# ANSIN.net
KiCad netlist of a schematic drawn in Altium Designer
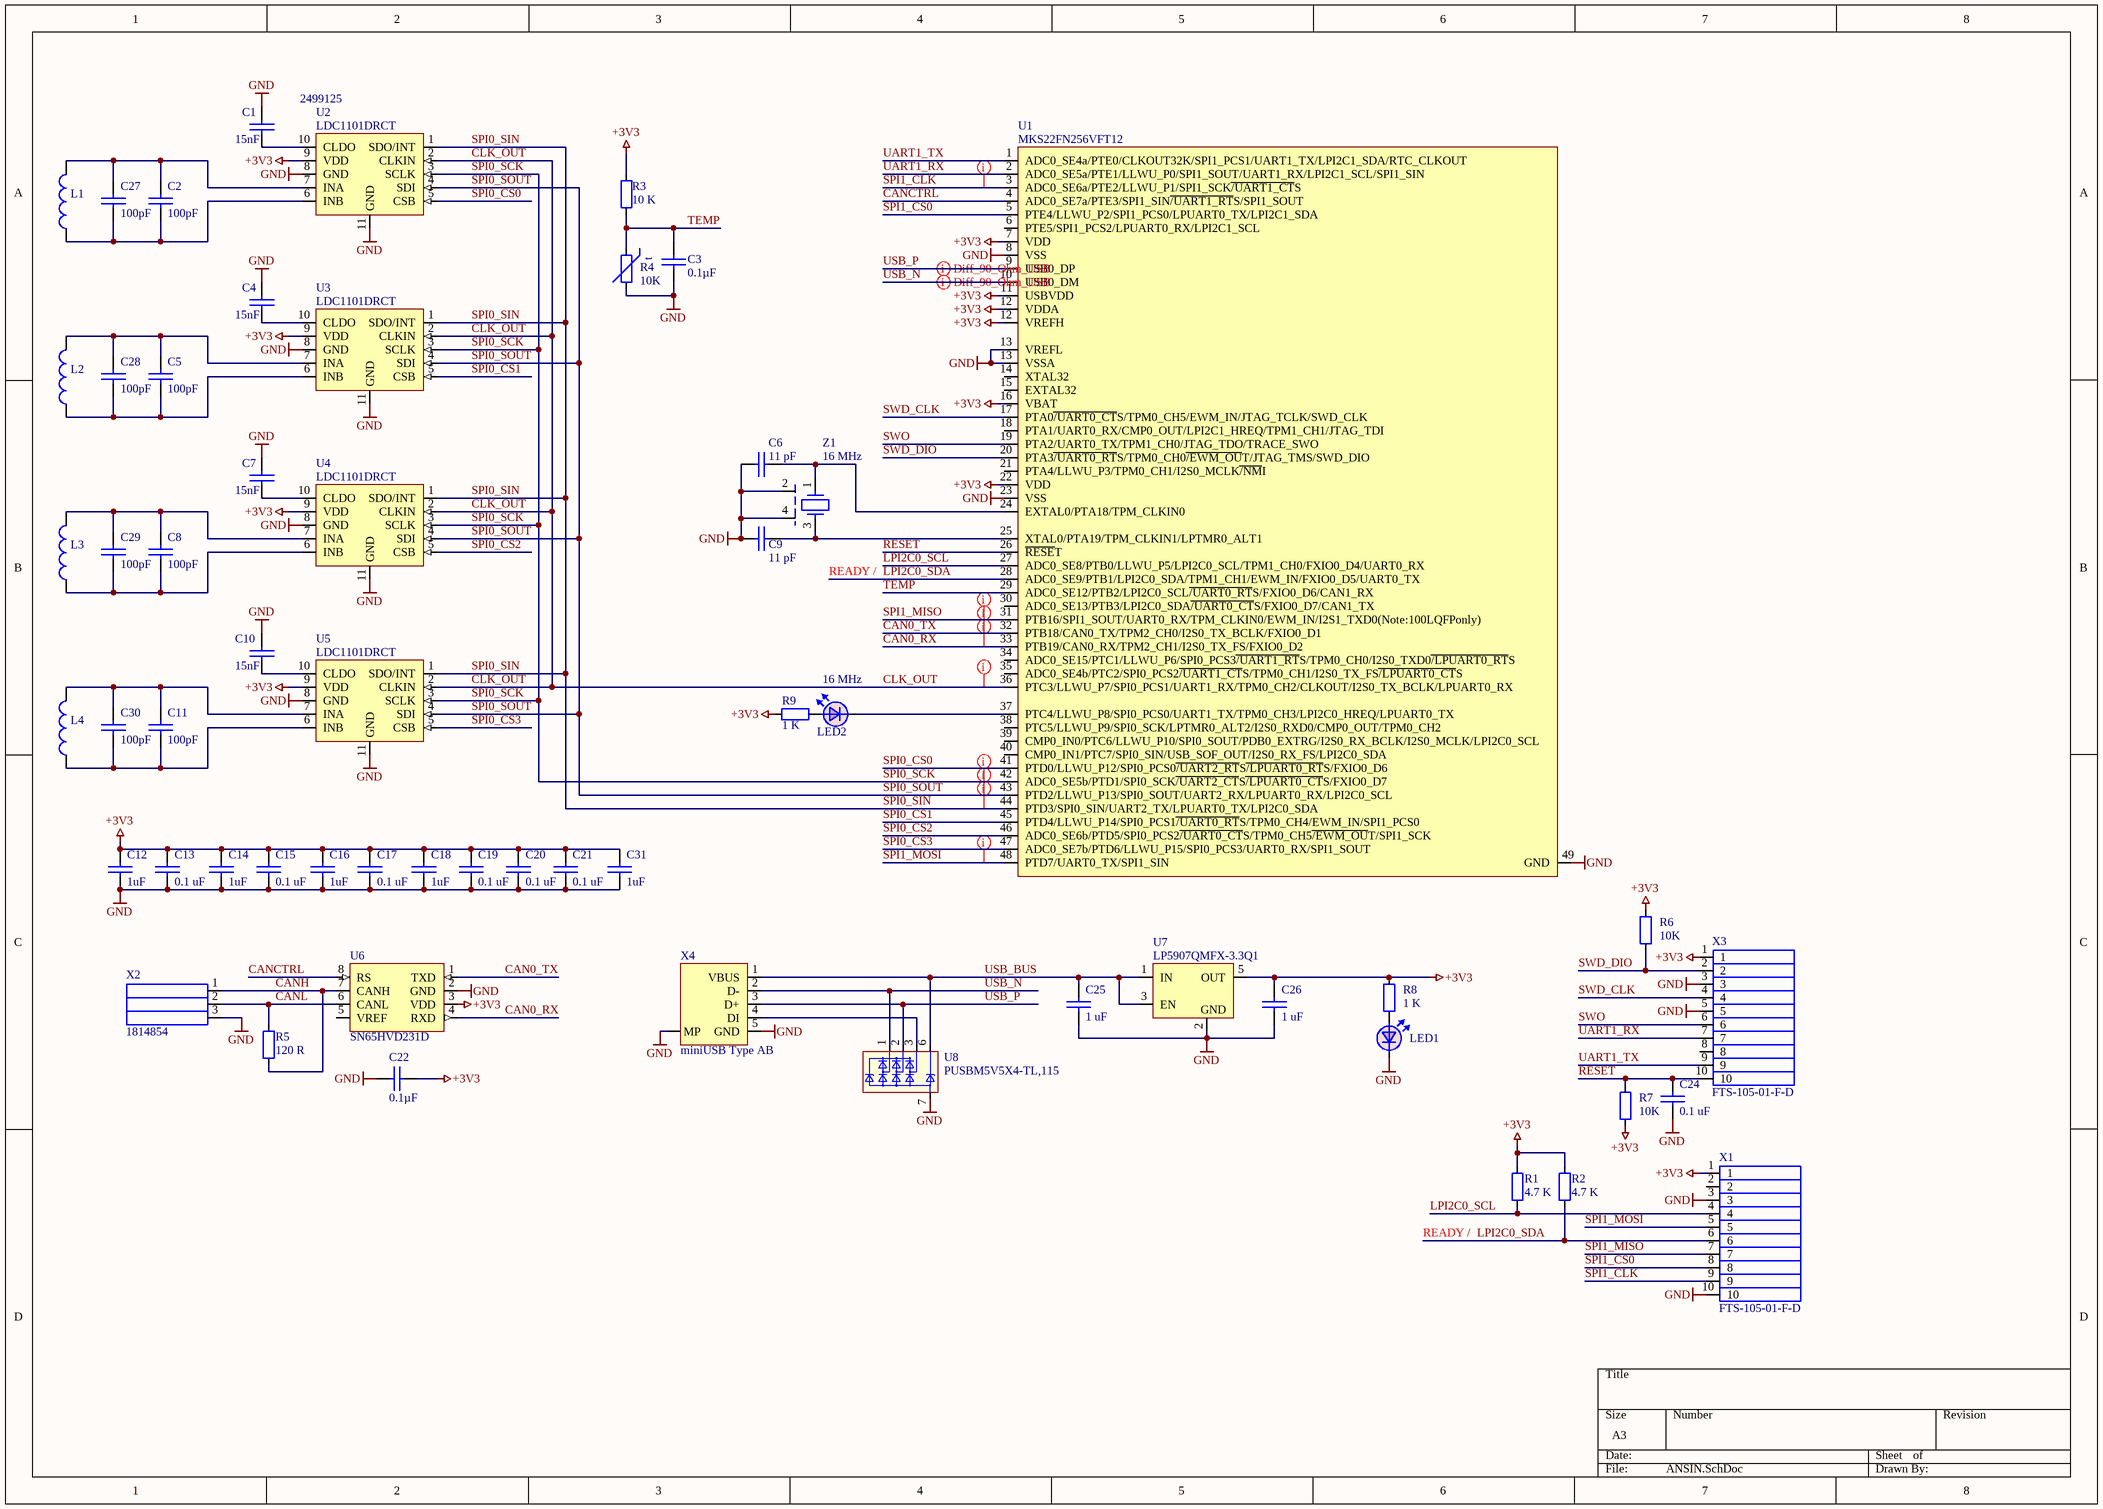
[diagram p0: ANSIN.SchDoc]

(export (version "E")
  (design (tool "Eeschema 10.0.6"))
  (components
    (comp (ref "C1")
      (value "15nF")
      (footprint "1005[0402]")
      (description "15 nF ±10%, 50V, X7R 0402, -55°C ~ 125°C")
      (fields
        (field (name "TOLERANCE") "±10%")
        (field (name "MANUFACTURER") "Murata Electronics North America")
      )
      (libsource (lib "ea_Capacitors") (part "GRM155R71H153KA12J"))
    )
    (comp (ref "C2")
      (value "100pF")
      (footprint "1005[0402]")
      (description "100pF ±1% 25V,High Q, C0G, NP0 0402")
      (fields (field (name "TOLERANCE") "±1%") (field (name "MANUFACTURER") "Kemet"))
      (libsource (lib "ea_Capacitors") (part "CBR04C101F3GAC"))
    )
    (comp (ref "C3")
      (value "0.1µF")
      (footprint "1608[0603]")
      (description "0.1 uF, 50V, 10% , X7R,  0603 SMD MLC Capacitor")
      (fields (field (name "TOLERANCE") "± 10%") (field (name "MANUFACTURER") "WALSIN"))
      (libsource (lib "ea_Capacitors") (part "CVNF100K0603-25"))
    )
    (comp (ref "C4")
      (value "15nF")
      (footprint "1005[0402]")
      (description "15 nF ±10%, 50V, X7R 0402, -55°C ~ 125°C")
      (fields
        (field (name "TOLERANCE") "±10%")
        (field (name "MANUFACTURER") "Murata Electronics North America")
      )
      (libsource (lib "ea_Capacitors") (part "GRM155R71H153KA12J"))
    )
    (comp (ref "C5")
      (value "100pF")
      (footprint "1005[0402]")
      (description "100pF ±1% 25V,High Q, C0G, NP0 0402")
      (fields (field (name "TOLERANCE") "±1%") (field (name "MANUFACTURER") "Kemet"))
      (libsource (lib "ea_Capacitors") (part "CBR04C101F3GAC"))
    )
    (comp (ref "C6")
      (value "11 pF")
      (footprint "1005[0402]")
      (description "11 pF, 25V, +-1%, NP0/COG, 0402, -55..+125")
      (fields (field (name "MANUFACTURER") "AVX Corporation") (field (name "TOLERANCE") "+-1%"))
      (libsource (lib "ea_Capacitors") (part "04023U110FAT2A"))
    )
    (comp (ref "C7")
      (value "15nF")
      (footprint "1005[0402]")
      (description "15 nF ±10%, 50V, X7R 0402, -55°C ~ 125°C")
      (fields
        (field (name "TOLERANCE") "±10%")
        (field (name "MANUFACTURER") "Murata Electronics North America")
      )
      (libsource (lib "ea_Capacitors") (part "GRM155R71H153KA12J"))
    )
    (comp (ref "C8")
      (value "100pF")
      (footprint "1005[0402]")
      (description "100pF ±1% 25V,High Q, C0G, NP0 0402")
      (fields (field (name "TOLERANCE") "±1%") (field (name "MANUFACTURER") "Kemet"))
      (libsource (lib "ea_Capacitors") (part "CBR04C101F3GAC"))
    )
    (comp (ref "C9")
      (value "11 pF")
      (footprint "1005[0402]")
      (description "11 pF, 25V, +-1%, NP0/COG, 0402, -55..+125")
      (fields (field (name "MANUFACTURER") "AVX Corporation") (field (name "TOLERANCE") "+-1%"))
      (libsource (lib "ea_Capacitors") (part "04023U110FAT2A"))
    )
    (comp (ref "C10")
      (value "15nF")
      (footprint "1005[0402]")
      (description "15 nF ±10%, 50V, X7R 0402, -55°C ~ 125°C")
      (fields
        (field (name "TOLERANCE") "±10%")
        (field (name "MANUFACTURER") "Murata Electronics North America")
      )
      (libsource (lib "ea_Capacitors") (part "GRM155R71H153KA12J"))
    )
    (comp (ref "C11")
      (value "100pF")
      (footprint "1005[0402]")
      (description "100pF ±1% 25V,High Q, C0G, NP0 0402")
      (fields (field (name "TOLERANCE") "±1%") (field (name "MANUFACTURER") "Kemet"))
      (libsource (lib "ea_Capacitors") (part "CBR04C101F3GAC"))
    )
    (comp (ref "C12")
      (value "1uF")
      (footprint "1005[0402]")
      (description "1 µF ±10% 16V, Low ESL X6S, 0402")
      (fields (field (name "TOLERANCE") "±10%") (field (name "MANUFACTURER") "TDK Corporation"))
      (libsource (lib "ea_Capacitors") (part "C1005X6S1C105K050BC"))
    )
    (comp (ref "C13")
      (value "0.1 uF")
      (footprint "1005[0402]")
      (description "0.1 uF, 10V, 10% , X5R,  0402, -55°C ~ 85°C")
      (fields (field (name "TOLERANCE") "+-10%") (field (name "MANUFACTURER") "Kemet"))
      (libsource (lib "ea_Capacitors") (part "C0402C104K8PACTU"))
    )
    (comp (ref "C14")
      (value "1uF")
      (footprint "1005[0402]")
      (description "1 µF ±10% 16V, Low ESL X6S, 0402")
      (fields (field (name "TOLERANCE") "±10%") (field (name "MANUFACTURER") "TDK Corporation"))
      (libsource (lib "ea_Capacitors") (part "C1005X6S1C105K050BC"))
    )
    (comp (ref "C15")
      (value "0.1 uF")
      (footprint "1005[0402]")
      (description "0.1 uF, 10V, 10% , X5R,  0402, -55°C ~ 85°C")
      (fields (field (name "TOLERANCE") "+-10%") (field (name "MANUFACTURER") "Kemet"))
      (libsource (lib "ea_Capacitors") (part "C0402C104K8PACTU"))
    )
    (comp (ref "C16")
      (value "1uF")
      (footprint "1005[0402]")
      (description "1 µF ±10% 16V, Low ESL X6S, 0402")
      (fields (field (name "TOLERANCE") "±10%") (field (name "MANUFACTURER") "TDK Corporation"))
      (libsource (lib "ea_Capacitors") (part "C1005X6S1C105K050BC"))
    )
    (comp (ref "C17")
      (value "0.1 uF")
      (footprint "1005[0402]")
      (description "0.1 uF, 10V, 10% , X5R,  0402, -55°C ~ 85°C")
      (fields (field (name "TOLERANCE") "+-10%") (field (name "MANUFACTURER") "Kemet"))
      (libsource (lib "ea_Capacitors") (part "C0402C104K8PACTU"))
    )
    (comp (ref "C18")
      (value "1uF")
      (footprint "1005[0402]")
      (description "1 µF ±10% 16V, Low ESL X6S, 0402")
      (fields (field (name "TOLERANCE") "±10%") (field (name "MANUFACTURER") "TDK Corporation"))
      (libsource (lib "ea_Capacitors") (part "C1005X6S1C105K050BC"))
    )
    (comp (ref "C19")
      (value "0.1 uF")
      (footprint "1005[0402]")
      (description "0.1 uF, 10V, 10% , X5R,  0402, -55°C ~ 85°C")
      (fields (field (name "TOLERANCE") "+-10%") (field (name "MANUFACTURER") "Kemet"))
      (libsource (lib "ea_Capacitors") (part "C0402C104K8PACTU"))
    )
    (comp (ref "C20")
      (value "0.1 uF")
      (footprint "1005[0402]")
      (description "0.1 uF, 10V, 10% , X5R,  0402, -55°C ~ 85°C")
      (fields (field (name "TOLERANCE") "+-10%") (field (name "MANUFACTURER") "Kemet"))
      (libsource (lib "ea_Capacitors") (part "C0402C104K8PACTU"))
    )
    (comp (ref "C21")
      (value "0.1 uF")
      (footprint "1005[0402]")
      (description "0.1 uF, 10V, 10% , X5R,  0402, -55°C ~ 85°C")
      (fields (field (name "TOLERANCE") "+-10%") (field (name "MANUFACTURER") "Kemet"))
      (libsource (lib "ea_Capacitors") (part "C0402C104K8PACTU"))
    )
    (comp (ref "C22")
      (value "0.1µF")
      (footprint "1608[0603]")
      (description "0.1 uF, 50V, 10% , X7R,  0603 SMD MLC Capacitor")
      (fields (field (name "TOLERANCE") "± 10%") (field (name "MANUFACTURER") "WALSIN"))
      (libsource (lib "ea_Capacitors") (part "CVNF100K0603-25"))
    )
    (comp (ref "C24")
      (value "0.1 uF")
      (footprint "1005[0402]")
      (description "0.1 uF, 10V, 10% , X5R,  0402, -55°C ~ 85°C")
      (fields (field (name "TOLERANCE") "+-10%") (field (name "MANUFACTURER") "Kemet"))
      (libsource (lib "ea_Capacitors") (part "C0402C104K8PACTU"))
    )
    (comp (ref "C25")
      (value "1 uF")
      (footprint "1608[0603]")
      (description "1.0 uF, 16V, 10%, X5R, 0603, -55..85 С")
      (fields (field (name "TOLERANCE") "10%") (field (name "MANUFACTURER") "Samsung"))
      (libsource (lib "ea_Capacitors") (part "CL10A105KO8NNNC"))
    )
    (comp (ref "C26")
      (value "1 uF")
      (footprint "1608[0603]")
      (description "1.0 uF, 16V, 10%, X5R, 0603, -55..85 С")
      (fields (field (name "TOLERANCE") "10%") (field (name "MANUFACTURER") "Samsung"))
      (libsource (lib "ea_Capacitors") (part "CL10A105KO8NNNC"))
    )
    (comp (ref "C27")
      (value "100pF")
      (footprint "1005[0402]")
      (description "100pF ±1% 25V,High Q, C0G, NP0 0402")
      (fields (field (name "TOLERANCE") "±1%") (field (name "MANUFACTURER") "Kemet"))
      (libsource (lib "ea_Capacitors") (part "CBR04C101F3GAC"))
    )
    (comp (ref "C28")
      (value "100pF")
      (footprint "1005[0402]")
      (description "100pF ±1% 25V,High Q, C0G, NP0 0402")
      (fields (field (name "TOLERANCE") "±1%") (field (name "MANUFACTURER") "Kemet"))
      (libsource (lib "ea_Capacitors") (part "CBR04C101F3GAC"))
    )
    (comp (ref "C29")
      (value "100pF")
      (footprint "1005[0402]")
      (description "100pF ±1% 25V,High Q, C0G, NP0 0402")
      (fields (field (name "TOLERANCE") "±1%") (field (name "MANUFACTURER") "Kemet"))
      (libsource (lib "ea_Capacitors") (part "CBR04C101F3GAC"))
    )
    (comp (ref "C30")
      (value "100pF")
      (footprint "1005[0402]")
      (description "100pF ±1% 25V,High Q, C0G, NP0 0402")
      (fields (field (name "TOLERANCE") "±1%") (field (name "MANUFACTURER") "Kemet"))
      (libsource (lib "ea_Capacitors") (part "CBR04C101F3GAC"))
    )
    (comp (ref "C31")
      (value "1uF")
      (footprint "1005[0402]")
      (description "1 µF ±10% 16V, Low ESL X6S, 0402")
      (fields (field (name "TOLERANCE") "±10%") (field (name "MANUFACTURER") "TDK Corporation"))
      (libsource (lib "ea_Capacitors") (part "C1005X6S1C105K050BC"))
    )
    (comp (ref "L1")
      (value "Coil")
      (footprint "Coil_4layers_8turns")
      (description "Coil_4layers_8turns")
      (libsource (lib "ea_SensorCoils") (part "Coil_4layers_8turns"))
    )
    (comp (ref "L2")
      (value "Coil")
      (footprint "Coil_4layers_8turns")
      (description "Coil_4layers_8turns")
      (libsource (lib "ea_SensorCoils") (part "Coil_4layers_8turns"))
    )
    (comp (ref "L3")
      (value "Coil")
      (footprint "Coil_4layers_8turns")
      (description "Coil_4layers_8turns")
      (libsource (lib "ea_SensorCoils") (part "Coil_4layers_8turns"))
    )
    (comp (ref "L4")
      (value "Coil")
      (footprint "Coil_4layers_8turns")
      (description "Coil_4layers_8turns")
      (libsource (lib "ea_SensorCoils") (part "Coil_4layers_8turns"))
    )
    (comp (ref "LED1")
      (value "SML-211UTT86")
      (footprint "0805 LED")
      (description "0805 red LED, hibright, 2 mA, 1.8V, 130°")
      (fields (field (name "MANUFACTURER") "Rohm") (field (name "PARTNUM") "511-1292-1-ND"))
      (libsource (lib "ea_Indicators") (part "SML-211UTT86"))
    )
    (comp (ref "LED2")
      (value "SML-211UTT86")
      (footprint "0805 LED")
      (description "0805 red LED, hibright, 2 mA, 1.8V, 130°")
      (fields (field (name "MANUFACTURER") "Rohm") (field (name "PARTNUM") "511-1292-1-ND"))
      (libsource (lib "ea_Indicators") (part "SML-211UTT86"))
    )
    (comp (ref "R1")
      (value "4.7 K")
      (footprint "0603")
      (description "4.7 K, 1%, 0603, SMD Resistor, Taped")
      (fields (field (name "MANUFACTURER") "Vishay") (field (name "TOLERANCE") "1%"))
      (libsource (lib "ea_Resistors") (part "RL0603K004.7-1"))
    )
    (comp (ref "R2")
      (value "4.7 K")
      (footprint "0603")
      (description "4.7 K, 1%, 0603, SMD Resistor, Taped")
      (fields (field (name "MANUFACTURER") "Vishay") (field (name "TOLERANCE") "1%"))
      (libsource (lib "ea_Resistors") (part "RL0603K004.7-1"))
    )
    (comp (ref "R3")
      (value "10 K")
      (footprint "0603")
      (description "10 K, 1%, 0603, SMD Resistor, Taped")
      (fields (field (name "MANUFACTURER") "Vishay Dale") (field (name "TOLERANCE") "1%"))
      (libsource (lib "ea_Resistors") (part "RL0603K010-1"))
    )
    (comp (ref "R4")
      (value "10K")
      (footprint "0805")
      (description "Thermistor 10k, 0805, NTC")
      (fields (field (name "MANUFACTURER") "Murata") (field (name "PARTNUM") "490-2456-1-ND"))
      (libsource (lib "ea_IC_sensors") (part "NCP21XV103J03RA"))
    )
    (comp (ref "R5")
      (value "120 R")
      (footprint "0603")
      (description "120 R, 1%, 0603, SMD Resistor, Taped")
      (fields (field (name "MANUFACTURER") "Vishay") (field (name "TOLERANCE") "1%"))
      (libsource (lib "ea_Resistors") (part "RL0603E120-1"))
    )
    (comp (ref "R6")
      (value "10K")
      (footprint "0402")
      (description "10 K, 0402, Thick Film, -55..+155")
      (fields (field (name "MANUFACTURER") "Rohm Semiconductor") (field (name "TOLERANCE") "5%"))
      (libsource (lib "ea_Resistors") (part "MCR01MZPJ103"))
    )
    (comp (ref "R7")
      (value "10K")
      (footprint "0402")
      (description "10 K, 0402, Thick Film, -55..+155")
      (fields (field (name "MANUFACTURER") "Rohm Semiconductor") (field (name "TOLERANCE") "5%"))
      (libsource (lib "ea_Resistors") (part "MCR01MZPJ103"))
    )
    (comp (ref "R8")
      (value "1 K")
      (footprint "0603")
      (description "1 K, 1%, 0603, SMD Resistor, Taped")
      (fields (field (name "MANUFACTURER") "Vishay") (field (name "TOLERANCE") "1%"))
      (libsource (lib "") (part "RL0603K001-1_1"))
    )
    (comp (ref "R9")
      (value "1 K")
      (footprint "0603")
      (description "1 K, 1%, 0603, SMD Resistor, Taped")
      (fields (field (name "MANUFACTURER") "Vishay") (field (name "TOLERANCE") "1%"))
      (libsource (lib "ea_Resistors") (part "RL0603K001-1"))
    )
    (comp (ref "U1")
      (value "MKS22FN256VFT12")
      (footprint "48-pin QFN NXP")
      (description "ARM® Cortex®-M4 Kinetis KS22 Microcontroller IC 32-Bit 120MHz 256KB (256K x 8) FLASH 48-QFN (7x7)")
      (fields (field (name "MANUFACTURER") "NXP USA Inc.") (field (name "PARTNUM") "MKS22FN256VFT12-ND"))
      (libsource (lib "ea_IC_CPU") (part "MKS22FN256VFT12"))
    )
    (comp (ref "U2")
      (value "LDC1101DRCT")
      (footprint "TI S-PVSON-N10")
      (description "Inductance-to-Digital Converter 16 b, 24 bit 150k, 180k SPI, -40°C ~ 125°C,  10-VSON (3x3)")
      (fields
        (field (name "MANUFACTURER") "Texas Instruments")
        (field (name "PARTNUM") "296-42280-1-ND")
        (field (name "SUPPLIER PART NUMBER 1") "2499125")
      )
      (libsource (lib "ea_IC_hall_gmr_sensors") (part "LDC1101DRCT"))
    )
    (comp (ref "U3")
      (value "LDC1101DRCT")
      (footprint "TI S-PVSON-N10")
      (description "Inductance-to-Digital Converter 16 b, 24 bit 150k, 180k SPI, -40°C ~ 125°C,  10-VSON (3x3)")
      (fields (field (name "MANUFACTURER") "Texas Instruments") (field (name "PARTNUM") "296-42280-1-ND"))
      (libsource (lib "ea_IC_hall_gmr_sensors") (part "LDC1101DRCT"))
    )
    (comp (ref "U4")
      (value "LDC1101DRCT")
      (footprint "TI S-PVSON-N10")
      (description "Inductance-to-Digital Converter 16 b, 24 bit 150k, 180k SPI, -40°C ~ 125°C,  10-VSON (3x3)")
      (fields (field (name "MANUFACTURER") "Texas Instruments") (field (name "PARTNUM") "296-42280-1-ND"))
      (libsource (lib "ea_IC_hall_gmr_sensors") (part "LDC1101DRCT"))
    )
    (comp (ref "U5")
      (value "LDC1101DRCT")
      (footprint "TI S-PVSON-N10")
      (description "Inductance-to-Digital Converter 16 b, 24 bit 150k, 180k SPI, -40°C ~ 125°C,  10-VSON (3x3)")
      (fields (field (name "MANUFACTURER") "Texas Instruments") (field (name "PARTNUM") "296-42280-1-ND"))
      (libsource (lib "ea_IC_hall_gmr_sensors") (part "LDC1101DRCT"))
    )
    (comp (ref "U6")
      (value "SN65HVD231D")
      (footprint "SO-8")
      (description "3.3-V CAN TRANSCEIVERS SO-8")
      (fields (field (name "MANUFACTURER") "Texas Instruments") (field (name "PARTNUM") "296-12206-5-ND"))
      (libsource (lib "ea_IC_Interfaces") (part "SN65HVD231D"))
    )
    (comp (ref "U7")
      (value "LP5907QMFX-3.3Q1")
      (footprint "SOT23-5")
      (description "LDO 3.3 V, 250 mA, Vin < 5.5V, Iq < 12uA, -40..+125 C, SOT23-5")
      (fields (field (name "MANUFACTURER") "Texas Instruments") (field (name "PARTNUM") "296-40365-1-ND"))
      (libsource (lib "ea_IC_Power_Reg_Ref_Sw") (part "LP5907QMFX-3.3Q1"))
    )
    (comp (ref "U8")
      (value "PUSBM5V5X4-TL,115")
      (footprint "DFN1616-6")
      (description "TVS DIODE 5.5VWM 12VC 6HXSON")
      (fields (field (name "MANUFACTURER") "NXP Semiconductors") (field (name "PARTNUM") "568-10921-1-ND"))
      (libsource (lib "ea_TVS_protection") (part "PUSBM5V5X4-TL,115"))
    )
    (comp (ref "X1")
      (value "FTS-105-01-F-D")
      (footprint "FTS-105-01-F-D")
      (description "Board-To-Board Connector, Vertical, FTS Series, Through Hole, Header, 10, 1.27 mm")
      (fields (field (name "MANUFACTURER") "SAMTEC") (field (name "PARTNUM") "1928242"))
      (libsource (lib "ea_JTAG_SWD") (part "FTS-105-01-F-D"))
    )
    (comp (ref "X2")
      (value "1814854")
      (footprint "1814854")
      (description "SSL Connector 3 Position Header, Male Pins Board to Cable/Wire 0.098\" (2.50mm) Solder")
      (fields (field (name "MANUFACTURER") "Phoenix Contact") (field (name "PARTNUM") "277-9957-1-ND"))
      (libsource (lib "ea_Connectors") (part "1814854"))
    )
    (comp (ref "X3")
      (value "FTS-105-01-F-D")
      (footprint "FTS-105-01-F-D")
      (description "Board-To-Board Connector, Vertical, FTS Series, Through Hole, Header, 10, 1.27 mm")
      (fields (field (name "MANUFACTURER") "SAMTEC") (field (name "PARTNUM") "1928242"))
      (libsource (lib "ea_JTAG_SWD") (part "FTS-105-01-F-D"))
    )
    (comp (ref "X4")
      (value "miniUSB Type AB")
      (footprint "USB AB 56579-0576 Molex")
      (description "SMD USB - OTG, miniUSB Type AB")
      (fields
        (field (name "MANUFACTURER") "Molex/Waldom Electronics Corp")
        (field (name "PARTNUM") "WM17122CT-ND")
      )
      (libsource (lib "ea_Connectors") (part "USB AB 56579-0576"))
    )
    (comp (ref "Z1")
      (value "16 MHz")
      (footprint "4-SMD 2.00mm x 1.60mm")
      (description "16 MHz, 9 pF, ±10ppm, 2.00mm x 1.60mm, -20°C ~ 70°C")
      (fields (field (name "MANUFACTURER") "Abracon LLC") (field (name "PARTNUM") "535-13598-1-ND"))
      (libsource (lib "ea_OSC_CLK_GEN") (part "ABM11-16.000MHZ-9-B1U-T"))
    )
  )
  (nets
    (net (code "1") (name "+3V3") (class "Default")
      (node (ref "C12") (pin "1") (pinfunction "1_1") (pintype "passive"))
      (node (ref "C13") (pin "1") (pinfunction "1_1") (pintype "passive"))
      (node (ref "C14") (pin "1") (pinfunction "1_1") (pintype "passive"))
      (node (ref "C15") (pin "1") (pinfunction "1_1") (pintype "passive"))
      (node (ref "C16") (pin "1") (pinfunction "1_1") (pintype "passive"))
      (node (ref "C17") (pin "1") (pinfunction "1_1") (pintype "passive"))
      (node (ref "C18") (pin "1") (pinfunction "1_1") (pintype "passive"))
      (node (ref "C19") (pin "1") (pinfunction "1_1") (pintype "passive"))
      (node (ref "C20") (pin "1") (pinfunction "1_1") (pintype "passive"))
      (node (ref "C21") (pin "1") (pinfunction "1_1") (pintype "passive"))
      (node (ref "C22") (pin "1") (pinfunction "1_1") (pintype "passive"))
      (node (ref "C26") (pin "1") (pinfunction "1_1") (pintype "passive"))
      (node (ref "C31") (pin "1") (pinfunction "1_1") (pintype "passive"))
      (node (ref "R1") (pin "2") (pinfunction "2_2") (pintype "passive"))
      (node (ref "R2") (pin "2") (pinfunction "2_2") (pintype "passive"))
      (node (ref "R3") (pin "2") (pinfunction "2_2") (pintype "passive"))
      (node (ref "R6") (pin "2") (pinfunction "2_2") (pintype "passive"))
      (node (ref "R7") (pin "1") (pinfunction "1_1") (pintype "passive"))
      (node (ref "R8") (pin "2") (pinfunction "2_2") (pintype "passive"))
      (node (ref "R9") (pin "2") (pinfunction "2_2") (pintype "passive"))
      (node (ref "U1") (pin "11") (pinfunction "USBVDD_11") (pintype "bidirectional"))
      (node (ref "U1") (pin "12") (pinfunction "VDDA_12") (pintype "power_in"))
      (node (ref "U1") (pin "16") (pinfunction "VBAT_16") (pintype "power_in"))
      (node (ref "U1") (pin "22") (pinfunction "VDD_22") (pintype "power_in"))
      (node (ref "U1") (pin "7") (pinfunction "VDD_7") (pintype "power_in"))
      (node (ref "U2") (pin "9") (pinfunction "VDD_9") (pintype "power_in"))
      (node (ref "U3") (pin "9") (pinfunction "VDD_9") (pintype "power_in"))
      (node (ref "U4") (pin "9") (pinfunction "VDD_9") (pintype "power_in"))
      (node (ref "U5") (pin "9") (pinfunction "VDD_9") (pintype "power_in"))
      (node (ref "U6") (pin "3") (pinfunction "VDD_3") (pintype "power_in"))
      (node (ref "U7") (pin "5") (pinfunction "OUT_5") (pintype "power_in"))
      (node (ref "X1") (pin "1") (pinfunction "1_1") (pintype "passive"))
      (node (ref "X3") (pin "1") (pinfunction "1_1") (pintype "passive"))
    )
    (net (code "2") (name "/CAN0_RX") (class "Default")
      (node (ref "U1") (pin "33") (pinfunction "PTB19/CAN0_RX/TPM2_CH1/I2S0_TX_FS/FXIO0_D2_33") (pintype "bidirectional"))
      (node (ref "U6") (pin "4") (pinfunction "RXD_4") (pintype "output"))
    )
    (net (code "3") (name "/CAN0_TX") (class "Default")
      (node (ref "U1") (pin "32") (pinfunction "PTB18/CAN0_TX/TPM2_CH0/I2S0_TX_BCLK/FXIO0_D1_32") (pintype "bidirectional"))
      (node (ref "U6") (pin "1") (pinfunction "TXD_1") (pintype "input"))
    )
    (net (code "4") (name "/CANCTRL") (class "Default")
      (node (ref "U1") (pin "4") (pinfunction "ADC0_SE7a/PTE3/SPI1_SIN~{/UART1_RT}S/SPI1_SOUT_4") (pintype "bidirectional"))
      (node (ref "U6") (pin "8") (pinfunction "RS_8") (pintype "input"))
    )
    (net (code "5") (name "/CANH") (class "Default")
      (node (ref "R5") (pin "1") (pinfunction "1_1") (pintype "passive"))
      (node (ref "U6") (pin "7") (pinfunction "CANH_7") (pintype "bidirectional"))
      (node (ref "X2") (pin "1") (pinfunction "1_1") (pintype "passive"))
    )
    (net (code "6") (name "/CANL") (class "Default")
      (node (ref "R5") (pin "2") (pinfunction "2_2") (pintype "passive"))
      (node (ref "U6") (pin "6") (pinfunction "CANL_6") (pintype "bidirectional"))
      (node (ref "X2") (pin "2") (pinfunction "2_2") (pintype "passive"))
    )
    (net (code "7") (name "/CLK_OUT") (class "Default")
      (node (ref "U1") (pin "36") (pinfunction "PTC3/LLWU_P7/SPI0_PCS1/UART1_RX/TPM0_CH2/CLKOUT/I2S0_TX_BCLK/LPUART0_RX_36") (pintype "bidirectional"))
      (node (ref "U2") (pin "2") (pinfunction "CLKIN_2") (pintype "input"))
      (node (ref "U3") (pin "2") (pinfunction "CLKIN_2") (pintype "input"))
      (node (ref "U4") (pin "2") (pinfunction "CLKIN_2") (pintype "input"))
      (node (ref "U5") (pin "2") (pinfunction "CLKIN_2") (pintype "input"))
    )
    (net (code "8") (name "/LPI2C0_SCL") (class "Default")
      (node (ref "R1") (pin "1") (pinfunction "1_1") (pintype "passive"))
      (node (ref "U1") (pin "27") (pinfunction "ADC0_SE8/PTB0/LLWU_P5/LPI2C0_SCL/TPM1_CH0/FXIO0_D4/UART0_RX_27") (pintype "bidirectional"))
      (node (ref "X1") (pin "4") (pinfunction "4_4") (pintype "passive"))
    )
    (net (code "9") (name "/LPI2C0_SDA") (class "Default")
      (node (ref "R2") (pin "1") (pinfunction "1_1") (pintype "passive"))
      (node (ref "U1") (pin "28") (pinfunction "ADC0_SE9/PTB1/LPI2C0_SDA/TPM1_CH1/EWM_IN/FXIO0_D5/UART0_TX_28") (pintype "bidirectional"))
      (node (ref "X1") (pin "6") (pinfunction "6_6") (pintype "power_in"))
    )
    (net (code "10") (name "/RESET") (class "Default")
      (node (ref "C24") (pin "1") (pinfunction "1_1") (pintype "passive"))
      (node (ref "R7") (pin "2") (pinfunction "2_2") (pintype "passive"))
      (node (ref "U1") (pin "26") (pinfunction "~{RESE}T_26") (pintype "bidirectional"))
      (node (ref "X3") (pin "10") (pinfunction "10_10") (pintype "power_in"))
    )
    (net (code "11") (name "/SPI0_CS0") (class "Default")
      (node (ref "U1") (pin "41") (pinfunction "PTD0/LLWU_P12/SPI0_PCS0~{/UART2_RT}S~{/LPUART0_RT}S/FXIO0_D6_41") (pintype "bidirectional"))
      (node (ref "U2") (pin "5") (pinfunction "CSB_5") (pintype "input"))
    )
    (net (code "12") (name "/SPI0_CS1") (class "Default")
      (node (ref "U1") (pin "45") (pinfunction "PTD4/LLWU_P14/SPI0_PCS1~{/UART0_RT}S/TPM0_CH4/EWM_IN/SPI1_PCS0_45") (pintype "bidirectional"))
      (node (ref "U3") (pin "5") (pinfunction "CSB_5") (pintype "input"))
    )
    (net (code "13") (name "/SPI0_CS2") (class "Default")
      (node (ref "U1") (pin "46") (pinfunction "ADC0_SE6b/PTD5/SPI0_PCS2~{/UART0_CT}S/TPM0_CH5~{/EWM_OU}T/SPI1_SCK_46") (pintype "bidirectional"))
      (node (ref "U4") (pin "5") (pinfunction "CSB_5") (pintype "input"))
    )
    (net (code "14") (name "/SPI0_CS3") (class "Default")
      (node (ref "U1") (pin "47") (pinfunction "ADC0_SE7b/PTD6/LLWU_P15/SPI0_PCS3/UART0_RX/SPI1_SOUT_47") (pintype "bidirectional"))
      (node (ref "U5") (pin "5") (pinfunction "CSB_5") (pintype "input"))
    )
    (net (code "15") (name "/SPI0_SCK") (class "Default")
      (node (ref "U1") (pin "42") (pinfunction "ADC0_SE5b/PTD1/SPI0_SCK~{/UART2_CT}S~{/LPUART0_CT}S/FXIO0_D7_42") (pintype "bidirectional"))
      (node (ref "U2") (pin "3") (pinfunction "SCLK_3") (pintype "input"))
      (node (ref "U3") (pin "3") (pinfunction "SCLK_3") (pintype "input"))
      (node (ref "U4") (pin "3") (pinfunction "SCLK_3") (pintype "input"))
      (node (ref "U5") (pin "3") (pinfunction "SCLK_3") (pintype "input"))
    )
    (net (code "16") (name "/SPI0_SIN") (class "Default")
      (node (ref "U1") (pin "44") (pinfunction "PTD3/SPI0_SIN/UART2_TX/LPUART0_TX/LPI2C0_SDA_44") (pintype "bidirectional"))
      (node (ref "U2") (pin "1") (pinfunction "SDO/INT_1") (pintype "tri_state"))
      (node (ref "U3") (pin "1") (pinfunction "SDO/INT_1") (pintype "tri_state"))
      (node (ref "U4") (pin "1") (pinfunction "SDO/INT_1") (pintype "tri_state"))
      (node (ref "U5") (pin "1") (pinfunction "SDO/INT_1") (pintype "tri_state"))
    )
    (net (code "17") (name "/SPI0_SOUT") (class "Default")
      (node (ref "U1") (pin "43") (pinfunction "PTD2/LLWU_P13/SPI0_SOUT/UART2_RX/LPUART0_RX/LPI2C0_SCL_43") (pintype "bidirectional"))
      (node (ref "U2") (pin "4") (pinfunction "SDI_4") (pintype "input"))
      (node (ref "U3") (pin "4") (pinfunction "SDI_4") (pintype "input"))
      (node (ref "U4") (pin "4") (pinfunction "SDI_4") (pintype "input"))
      (node (ref "U5") (pin "4") (pinfunction "SDI_4") (pintype "input"))
    )
    (net (code "18") (name "/SPI1_CLK") (class "Default")
      (node (ref "U1") (pin "3") (pinfunction "ADC0_SE6a/PTE2/LLWU_P1/SPI1_SCK~{/UART1_CT}S_3") (pintype "bidirectional"))
      (node (ref "X1") (pin "9") (pinfunction "9_9") (pintype "power_in"))
    )
    (net (code "19") (name "/SPI1_CS0") (class "Default")
      (node (ref "U1") (pin "5") (pinfunction "PTE4/LLWU_P2/SPI1_PCS0/LPUART0_TX/LPI2C1_SDA_5") (pintype "bidirectional"))
      (node (ref "X1") (pin "8") (pinfunction "8_8") (pintype "power_in"))
    )
    (net (code "20") (name "/SPI1_MISO") (class "Default")
      (node (ref "U1") (pin "31") (pinfunction "PTB16/SPI1_SOUT/UART0_RX/TPM_CLKIN0/EWM_IN/I2S1_TXD0(Note:100LQFPonly)_31") (pintype "bidirectional"))
      (node (ref "X1") (pin "7") (pinfunction "7_7") (pintype "power_in"))
    )
    (net (code "21") (name "/SPI1_MOSI") (class "Default")
      (node (ref "U1") (pin "48") (pinfunction "PTD7/UART0_TX/SPI1_SIN_48") (pintype "bidirectional"))
      (node (ref "X1") (pin "5") (pinfunction "5_5") (pintype "power_in"))
    )
    (net (code "22") (name "/SWD_CLK") (class "Default")
      (node (ref "U1") (pin "17") (pinfunction "PTA0~{/UART0_CT}S/TPM0_CH5/EWM_IN/JTAG_TCLK/SWD_CLK_17") (pintype "bidirectional"))
      (node (ref "X3") (pin "4") (pinfunction "4_4") (pintype "passive"))
    )
    (net (code "23") (name "/SWD_DIO") (class "Default")
      (node (ref "R6") (pin "1") (pinfunction "1_1") (pintype "passive"))
      (node (ref "U1") (pin "20") (pinfunction "PTA3~{/UART0_RT}S/TPM0_CH0~{/EWM_OU}T/JTAG_TMS/SWD_DIO_20") (pintype "bidirectional"))
      (node (ref "X3") (pin "2") (pinfunction "2_2") (pintype "passive"))
    )
    (net (code "24") (name "/SWO") (class "Default")
      (node (ref "U1") (pin "19") (pinfunction "PTA2/UART0_TX/TPM1_CH0/JTAG_TDO/TRACE_SWO_19") (pintype "bidirectional"))
      (node (ref "X3") (pin "6") (pinfunction "6_6") (pintype "power_in"))
    )
    (net (code "25") (name "/TEMP") (class "Default")
      (node (ref "C3") (pin "2") (pinfunction "2_2") (pintype "passive"))
      (node (ref "R3") (pin "1") (pinfunction "1_1") (pintype "passive"))
      (node (ref "R4") (pin "2") (pinfunction "2_2") (pintype "passive"))
      (node (ref "U1") (pin "29") (pinfunction "ADC0_SE12/PTB2/LPI2C0_SCL~{/UART0_RT}S/FXIO0_D6/CAN1_RX_29") (pintype "bidirectional"))
    )
    (net (code "26") (name "/UART1_RX") (class "Default")
      (node (ref "U1") (pin "2") (pinfunction "ADC0_SE5a/PTE1/LLWU_P0/SPI1_SOUT/UART1_RX/LPI2C1_SCL/SPI1_SIN_2") (pintype "bidirectional"))
      (node (ref "X3") (pin "7") (pinfunction "7_7") (pintype "power_in"))
    )
    (net (code "27") (name "/UART1_TX") (class "Default")
      (node (ref "U1") (pin "1") (pinfunction "ADC0_SE4a/PTE0/CLKOUT32K/SPI1_PCS1/UART1_TX/LPI2C1_SDA/RTC_CLKOUT_1") (pintype "bidirectional"))
      (node (ref "X3") (pin "9") (pinfunction "9_9") (pintype "power_in"))
    )
    (net (code "28") (name "/USB_BUS") (class "Default")
      (node (ref "C25") (pin "1") (pinfunction "1_1") (pintype "passive"))
      (node (ref "U7") (pin "1") (pinfunction "IN_1") (pintype "power_in"))
      (node (ref "U7") (pin "3") (pinfunction "EN_3") (pintype "power_in"))
      (node (ref "U8") (pin "6") (pinfunction "6_6") (pintype "passive"))
      (node (ref "X4") (pin "1") (pinfunction "VBUS_1") (pintype "power_in"))
    )
    (net (code "29") (name "/USB_N") (class "Default")
      (node (ref "U1") (pin "10") (pinfunction "USB0_DM_10") (pintype "bidirectional"))
      (node (ref "U8") (pin "1") (pinfunction "1_1") (pintype "passive"))
      (node (ref "X4") (pin "2") (pinfunction "D-_2") (pintype "bidirectional"))
    )
    (net (code "30") (name "/USB_P") (class "Default")
      (node (ref "U1") (pin "9") (pinfunction "USB0_DP_9") (pintype "bidirectional"))
      (node (ref "U8") (pin "2") (pinfunction "2_2") (pintype "passive"))
      (node (ref "X4") (pin "3") (pinfunction "D+_3") (pintype "bidirectional"))
    )
    (net (code "31") (name "GND") (class "Default")
      (node (ref "C1") (pin "1") (pinfunction "1_1") (pintype "passive"))
      (node (ref "C10") (pin "1") (pinfunction "1_1") (pintype "passive"))
      (node (ref "C12") (pin "2") (pinfunction "2_2") (pintype "passive"))
      (node (ref "C13") (pin "2") (pinfunction "2_2") (pintype "passive"))
      (node (ref "C14") (pin "2") (pinfunction "2_2") (pintype "passive"))
      (node (ref "C15") (pin "2") (pinfunction "2_2") (pintype "passive"))
      (node (ref "C16") (pin "2") (pinfunction "2_2") (pintype "passive"))
      (node (ref "C17") (pin "2") (pinfunction "2_2") (pintype "passive"))
      (node (ref "C18") (pin "2") (pinfunction "2_2") (pintype "passive"))
      (node (ref "C19") (pin "2") (pinfunction "2_2") (pintype "passive"))
      (node (ref "C20") (pin "2") (pinfunction "2_2") (pintype "passive"))
      (node (ref "C21") (pin "2") (pinfunction "2_2") (pintype "passive"))
      (node (ref "C22") (pin "2") (pinfunction "2_2") (pintype "passive"))
      (node (ref "C24") (pin "2") (pinfunction "2_2") (pintype "passive"))
      (node (ref "C25") (pin "2") (pinfunction "2_2") (pintype "passive"))
      (node (ref "C26") (pin "2") (pinfunction "2_2") (pintype "passive"))
      (node (ref "C3") (pin "1") (pinfunction "1_1") (pintype "passive"))
      (node (ref "C31") (pin "2") (pinfunction "2_2") (pintype "passive"))
      (node (ref "C4") (pin "1") (pinfunction "1_1") (pintype "passive"))
      (node (ref "C6") (pin "2") (pinfunction "2_2") (pintype "passive"))
      (node (ref "C7") (pin "1") (pinfunction "1_1") (pintype "passive"))
      (node (ref "C9") (pin "2") (pinfunction "2_2") (pintype "passive"))
      (node (ref "LED1") (pin "2") (pinfunction "2_2") (pintype "passive"))
      (node (ref "R4") (pin "1") (pinfunction "1_1") (pintype "passive"))
      (node (ref "U1") (pin "13") (pinfunction "VREFL_13") (pintype "bidirectional"))
      (node (ref "U1") (pin "23") (pinfunction "VSS_23") (pintype "power_in"))
      (node (ref "U1") (pin "49") (pinfunction "GND_49") (pintype "passive"))
      (node (ref "U1") (pin "8") (pinfunction "VSS_8") (pintype "power_in"))
      (node (ref "U2") (pin "11") (pinfunction "GND_11") (pintype "passive"))
      (node (ref "U2") (pin "8") (pinfunction "GND_8") (pintype "passive"))
      (node (ref "U3") (pin "11") (pinfunction "GND_11") (pintype "passive"))
      (node (ref "U3") (pin "8") (pinfunction "GND_8") (pintype "passive"))
      (node (ref "U4") (pin "11") (pinfunction "GND_11") (pintype "passive"))
      (node (ref "U4") (pin "8") (pinfunction "GND_8") (pintype "passive"))
      (node (ref "U5") (pin "11") (pinfunction "GND_11") (pintype "passive"))
      (node (ref "U5") (pin "8") (pinfunction "GND_8") (pintype "passive"))
      (node (ref "U6") (pin "2") (pinfunction "GND_2") (pintype "power_in"))
      (node (ref "U7") (pin "2") (pinfunction "GND_2") (pintype "power_in"))
      (node (ref "U8") (pin "7") (pinfunction "7_7") (pintype "passive"))
      (node (ref "X1") (pin "10") (pinfunction "10_10") (pintype "power_in"))
      (node (ref "X1") (pin "3") (pinfunction "3_3") (pintype "passive"))
      (node (ref "X2") (pin "3") (pinfunction "3_3") (pintype "passive"))
      (node (ref "X3") (pin "3") (pinfunction "3_3") (pintype "passive"))
      (node (ref "X3") (pin "5") (pinfunction "5_5") (pintype "power_in"))
      (node (ref "X4") (pin "5") (pinfunction "GND_5") (pintype "power_in"))
      (node (ref "X4") (pin "MP") (pinfunction "MP_MP") (pintype "passive"))
      (node (ref "Z1") (pin "2") (pinfunction "2_2") (pintype "passive"))
      (node (ref "Z1") (pin "4") (pinfunction "4_4") (pintype "passive"))
    )
    (net (code "32") (name "Net-(LED1-Pad1)") (class "Default")
      (node (ref "LED1") (pin "1") (pinfunction "1_1") (pintype "passive"))
      (node (ref "R8") (pin "1") (pinfunction "1_1") (pintype "passive"))
    )
    (net (code "33") (name "Net-(LED2-Pad1)") (class "Default")
      (node (ref "LED2") (pin "1") (pinfunction "1_1") (pintype "passive"))
      (node (ref "R9") (pin "1") (pinfunction "1_1") (pintype "passive"))
    )
    (net (code "34") (name "Net-(U1-EXTAL0{slash}PTA18{slash}TPM_CLKIN0)") (class "Default")
      (node (ref "C6") (pin "1") (pinfunction "1_1") (pintype "passive"))
      (node (ref "U1") (pin "24") (pinfunction "EXTAL0/PTA18/TPM_CLKIN0_24") (pintype "bidirectional"))
      (node (ref "Z1") (pin "1") (pinfunction "1_1") (pintype "passive"))
    )
    (net (code "35") (name "Net-(U1-PTC4{slash}LLWU_P8{slash}SPI0_PCS0{slash}UART1_TX{slash}TPM0_CH3{slash}LPI2C0_HREQ{slash}LPUART0_TX)") (class "Default")
      (node (ref "LED2") (pin "2") (pinfunction "2_2") (pintype "passive"))
      (node (ref "U1") (pin "37") (pinfunction "PTC4/LLWU_P8/SPI0_PCS0/UART1_TX/TPM0_CH3/LPI2C0_HREQ/LPUART0_TX_37") (pintype "bidirectional"))
    )
    (net (code "36") (name "Net-(U1-XTAL0{slash}PTA19{slash}TPM_CLKIN1{slash}LPTMR0_ALT1)") (class "Default")
      (node (ref "C9") (pin "1") (pinfunction "1_1") (pintype "passive"))
      (node (ref "U1") (pin "25") (pinfunction "XTAL0/PTA19/TPM_CLKIN1/LPTMR0_ALT1_25") (pintype "bidirectional"))
      (node (ref "Z1") (pin "3") (pinfunction "3_3") (pintype "passive"))
    )
    (net (code "37") (name "Net-(U2-CLDO)") (class "Default")
      (node (ref "C1") (pin "2") (pinfunction "2_2") (pintype "passive"))
      (node (ref "U2") (pin "10") (pinfunction "CLDO_10") (pintype "passive"))
    )
    (net (code "38") (name "Net-(U2-INA)") (class "Default")
      (node (ref "C2") (pin "1") (pinfunction "1_1") (pintype "passive"))
      (node (ref "C27") (pin "1") (pinfunction "1_1") (pintype "passive"))
      (node (ref "L1") (pin "2") (pinfunction "2_2") (pintype "passive"))
      (node (ref "U2") (pin "7") (pinfunction "INA_7") (pintype "passive"))
    )
    (net (code "39") (name "Net-(U2-INB)") (class "Default")
      (node (ref "C2") (pin "2") (pinfunction "2_2") (pintype "passive"))
      (node (ref "C27") (pin "2") (pinfunction "2_2") (pintype "passive"))
      (node (ref "L1") (pin "1") (pinfunction "1_1") (pintype "passive"))
      (node (ref "U2") (pin "6") (pinfunction "INB_6") (pintype "passive"))
    )
    (net (code "40") (name "Net-(U3-CLDO)") (class "Default")
      (node (ref "C4") (pin "2") (pinfunction "2_2") (pintype "passive"))
      (node (ref "U3") (pin "10") (pinfunction "CLDO_10") (pintype "passive"))
    )
    (net (code "41") (name "Net-(U3-INA)") (class "Default")
      (node (ref "C28") (pin "1") (pinfunction "1_1") (pintype "passive"))
      (node (ref "C5") (pin "1") (pinfunction "1_1") (pintype "passive"))
      (node (ref "L2") (pin "2") (pinfunction "2_2") (pintype "passive"))
      (node (ref "U3") (pin "7") (pinfunction "INA_7") (pintype "passive"))
    )
    (net (code "42") (name "Net-(U3-INB)") (class "Default")
      (node (ref "C28") (pin "2") (pinfunction "2_2") (pintype "passive"))
      (node (ref "C5") (pin "2") (pinfunction "2_2") (pintype "passive"))
      (node (ref "L2") (pin "1") (pinfunction "1_1") (pintype "passive"))
      (node (ref "U3") (pin "6") (pinfunction "INB_6") (pintype "passive"))
    )
    (net (code "43") (name "Net-(U4-CLDO)") (class "Default")
      (node (ref "C7") (pin "2") (pinfunction "2_2") (pintype "passive"))
      (node (ref "U4") (pin "10") (pinfunction "CLDO_10") (pintype "passive"))
    )
    (net (code "44") (name "Net-(U4-INA)") (class "Default")
      (node (ref "C29") (pin "1") (pinfunction "1_1") (pintype "passive"))
      (node (ref "C8") (pin "1") (pinfunction "1_1") (pintype "passive"))
      (node (ref "L3") (pin "2") (pinfunction "2_2") (pintype "passive"))
      (node (ref "U4") (pin "7") (pinfunction "INA_7") (pintype "passive"))
    )
    (net (code "45") (name "Net-(U4-INB)") (class "Default")
      (node (ref "C29") (pin "2") (pinfunction "2_2") (pintype "passive"))
      (node (ref "C8") (pin "2") (pinfunction "2_2") (pintype "passive"))
      (node (ref "L3") (pin "1") (pinfunction "1_1") (pintype "passive"))
      (node (ref "U4") (pin "6") (pinfunction "INB_6") (pintype "passive"))
    )
    (net (code "46") (name "Net-(U5-CLDO)") (class "Default")
      (node (ref "C10") (pin "2") (pinfunction "2_2") (pintype "passive"))
      (node (ref "U5") (pin "10") (pinfunction "CLDO_10") (pintype "passive"))
    )
    (net (code "47") (name "Net-(U5-INA)") (class "Default")
      (node (ref "C11") (pin "1") (pinfunction "1_1") (pintype "passive"))
      (node (ref "C30") (pin "1") (pinfunction "1_1") (pintype "passive"))
      (node (ref "L4") (pin "2") (pinfunction "2_2") (pintype "passive"))
      (node (ref "U5") (pin "7") (pinfunction "INA_7") (pintype "passive"))
    )
    (net (code "48") (name "Net-(U5-INB)") (class "Default")
      (node (ref "C11") (pin "2") (pinfunction "2_2") (pintype "passive"))
      (node (ref "C30") (pin "2") (pinfunction "2_2") (pintype "passive"))
      (node (ref "L4") (pin "1") (pinfunction "1_1") (pintype "passive"))
      (node (ref "U5") (pin "6") (pinfunction "INB_6") (pintype "passive"))
    )
    (net (code "49") (name "Net-(X4-DI)") (class "Default")
      (node (ref "U8") (pin "3") (pinfunction "3_3") (pintype "passive"))
      (node (ref "X4") (pin "4") (pinfunction "DI_4") (pintype "bidirectional"))
    )
    (net (code "50") (name "unconnected-(U1-ADC0_SE4b{slash}PTC2{slash}SPI0_PCS2~{{slash}UART1_CT}S{slash}TPM0_CH1{slash}I2S0_TX_FS~{{slash}LPUART0_CT}S-Pad35)") (class "Default")
      (node (ref "U1") (pin "35") (pinfunction "ADC0_SE4b/PTC2/SPI0_PCS2~{/UART1_CT}S/TPM0_CH1/I2S0_TX_FS~{/LPUART0_CT}S_35") (pintype "bidirectional"))
    )
    (net (code "51") (name "unconnected-(U1-ADC0_SE13{slash}PTB3{slash}LPI2C0_SDA~{{slash}UART0_CT}S{slash}FXIO0_D7{slash}CAN1_TX-Pad30)") (class "Default")
      (node (ref "U1") (pin "30") (pinfunction "ADC0_SE13/PTB3/LPI2C0_SDA~{/UART0_CT}S/FXIO0_D7/CAN1_TX_30") (pintype "bidirectional"))
    )
    (net (code "52") (name "unconnected-(U1-ADC0_SE15{slash}PTC1{slash}LLWU_P6{slash}SPI0_PCS3~{{slash}UART1_RT}S{slash}TPM0_CH0{slash}I2S0_TXD0~{{slash}LPUART0_RT}S-Pad34)") (class "Default")
      (node (ref "U1") (pin "34") (pinfunction "ADC0_SE15/PTC1/LLWU_P6/SPI0_PCS3~{/UART1_RT}S/TPM0_CH0/I2S0_TXD0~{/LPUART0_RT}S_34") (pintype "bidirectional"))
    )
    (net (code "53") (name "unconnected-(U1-CMP0_IN0{slash}PTC6{slash}LLWU_P10{slash}SPI0_SOUT{slash}PDB0_EXTRG{slash}I2S0_RX_BCLK{slash}I2S0_MCLK{slash}LPI2C0_SCL-Pad39)") (class "Default")
      (node (ref "U1") (pin "39") (pinfunction "CMP0_IN0/PTC6/LLWU_P10/SPI0_SOUT/PDB0_EXTRG/I2S0_RX_BCLK/I2S0_MCLK/LPI2C0_SCL_39") (pintype "bidirectional"))
    )
    (net (code "54") (name "unconnected-(U1-CMP0_IN1{slash}PTC7{slash}SPI0_SIN{slash}USB_SOF_OUT{slash}I2S0_RX_FS{slash}LPI2C0_SDA-Pad40)") (class "Default")
      (node (ref "U1") (pin "40") (pinfunction "CMP0_IN1/PTC7/SPI0_SIN/USB_SOF_OUT/I2S0_RX_FS/LPI2C0_SDA_40") (pintype "bidirectional"))
    )
    (net (code "55") (name "unconnected-(U1-EXTAL32-Pad15)") (class "Default")
      (node (ref "U1") (pin "15") (pinfunction "EXTAL32_15") (pintype "bidirectional"))
    )
    (net (code "56") (name "unconnected-(U1-PTA1{slash}UART0_RX{slash}CMP0_OUT{slash}LPI2C1_HREQ{slash}TPM1_CH1{slash}JTAG_TDI-Pad18)") (class "Default")
      (node (ref "U1") (pin "18") (pinfunction "PTA1/UART0_RX/CMP0_OUT/LPI2C1_HREQ/TPM1_CH1/JTAG_TDI_18") (pintype "bidirectional"))
    )
    (net (code "57") (name "unconnected-(U1-PTA4{slash}LLWU_P3{slash}TPM0_CH1{slash}I2S0_MCLK~{{slash}NM}I-Pad21)") (class "Default")
      (node (ref "U1") (pin "21") (pinfunction "PTA4/LLWU_P3/TPM0_CH1/I2S0_MCLK~{/NM}I_21") (pintype "bidirectional"))
    )
    (net (code "58") (name "unconnected-(U1-PTC5{slash}LLWU_P9{slash}SPI0_SCK{slash}LPTMR0_ALT2{slash}I2S0_RXD0{slash}CMP0_OUT{slash}TPM0_CH2-Pad38)") (class "Default")
      (node (ref "U1") (pin "38") (pinfunction "PTC5/LLWU_P9/SPI0_SCK/LPTMR0_ALT2/I2S0_RXD0/CMP0_OUT/TPM0_CH2_38") (pintype "bidirectional"))
    )
    (net (code "59") (name "unconnected-(U1-PTE5{slash}SPI1_PCS2{slash}LPUART0_RX{slash}LPI2C1_SCL-Pad6)") (class "Default")
      (node (ref "U1") (pin "6") (pinfunction "PTE5/SPI1_PCS2/LPUART0_RX/LPI2C1_SCL_6") (pintype "bidirectional"))
    )
    (net (code "60") (name "unconnected-(U1-XTAL32-Pad14)") (class "Default")
      (node (ref "U1") (pin "14") (pinfunction "XTAL32_14") (pintype "bidirectional"))
    )
    (net (code "61") (name "unconnected-(U6-VREF-Pad5)") (class "Default")
      (node (ref "U6") (pin "5") (pinfunction "VREF_5") (pintype "passive"))
    )
    (net (code "62") (name "unconnected-(X1-Pad2)") (class "Default")
      (node (ref "X1") (pin "2") (pinfunction "2_2") (pintype "passive"))
    )
    (net (code "63") (name "unconnected-(X3-Pad8)") (class "Default")
      (node (ref "X3") (pin "8") (pinfunction "8_8") (pintype "power_in"))
    )
  )
)
